# L-D5019-08-01.net
KiCad netlist of a schematic drawn in Altium Designer
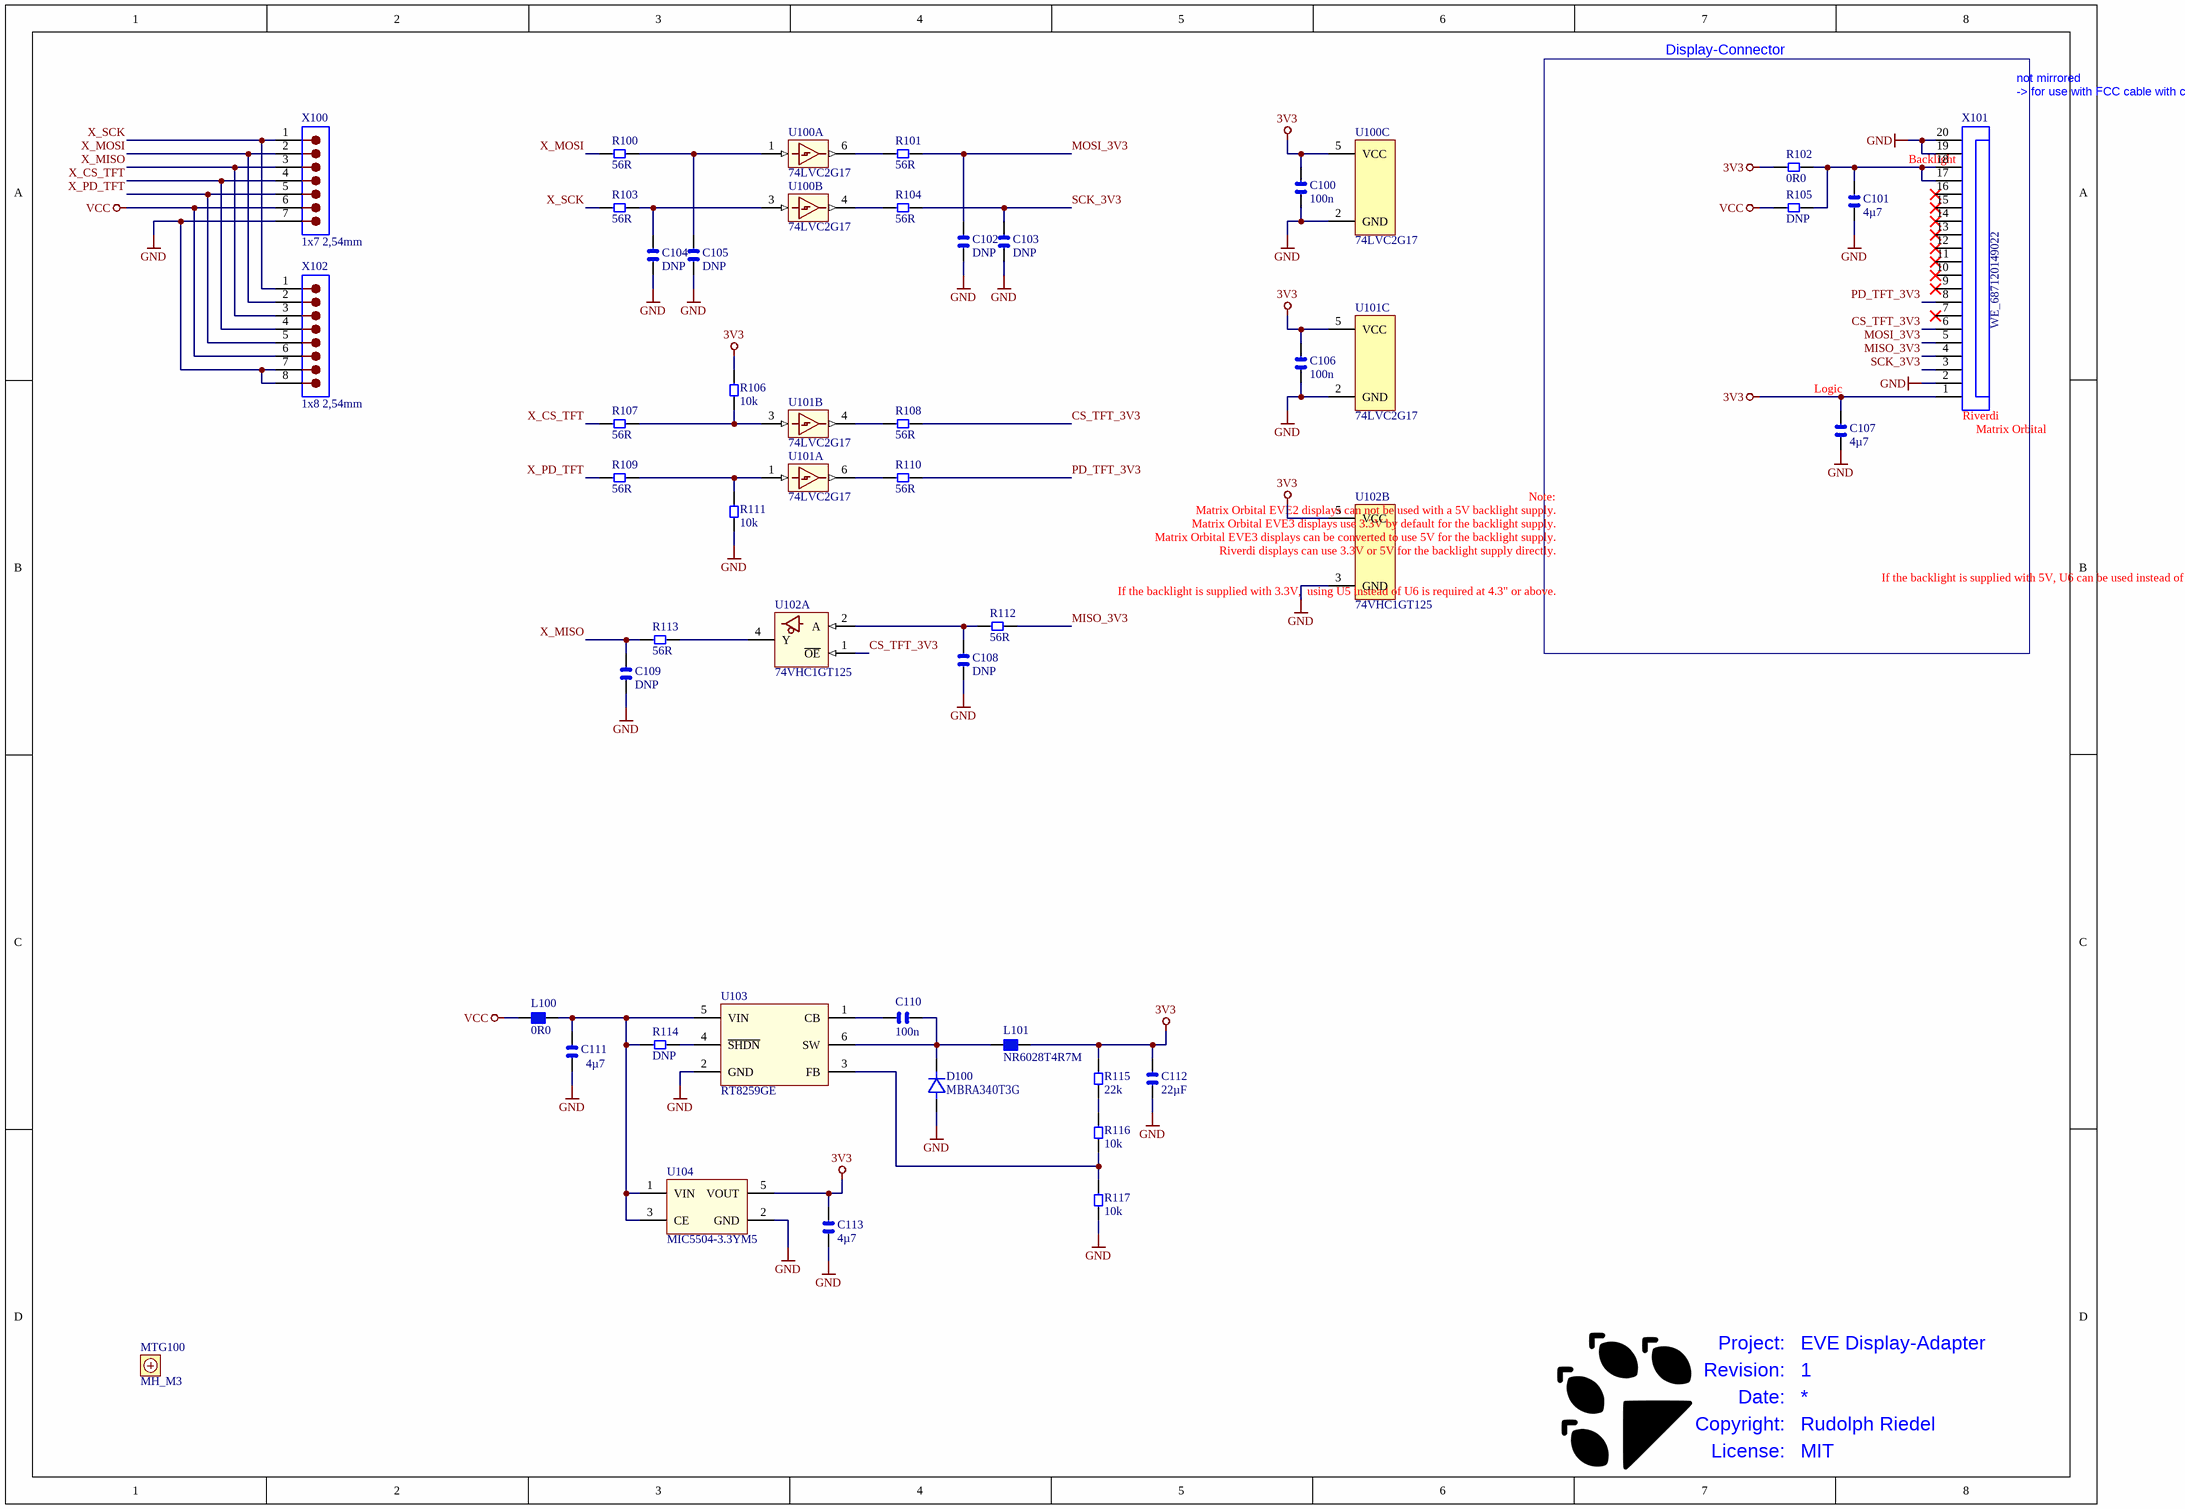
[diagram p0: L-D5019-08-01.SchDoc]

(export (version "E")
  (design (tool "Eeschema 10.0.6"))
  (components
    (comp (ref "C100")
      (value "100n")
      (footprint "CAPC2012X14L")
      (description "0805 Chip Capacitor")
      (fields (field (name "PART NUMBER") "CAPC_0805") (field (name "EDITOR") "rriedel"))
      (libsource (lib "HW-Labor_GF") (part "CAP_2_V2"))
    )
    (comp (ref "C101")
      (value "4µ7")
      (footprint "CAPC2012X14L")
      (description "0805 Chip Capacitor")
      (fields (field (name "PART NUMBER") "CAPC_0805") (field (name "ERSTELLER") "rriedel"))
      (libsource (lib "HW-Labor_GF") (part "CAP_2_V2"))
    )
    (comp (ref "C102")
      (value "DNP")
      (footprint "CAPC2012X14L")
      (description "0805 Chip Capacitor")
      (fields (field (name "PART NUMBER") "CAPC_0805") (field (name "EDITOR") "rriedel"))
      (libsource (lib "HW-Labor_GF") (part "CAP_2_V2"))
    )
    (comp (ref "C103")
      (value "DNP")
      (footprint "CAPC2012X14L")
      (description "0805 Chip Capacitor")
      (fields (field (name "PART NUMBER") "CAPC_0805") (field (name "EDITOR") "rriedel"))
      (libsource (lib "HW-Labor_GF") (part "CAP_2_V2"))
    )
    (comp (ref "C104")
      (value "DNP")
      (footprint "CAPC2012X14L")
      (description "0805 Chip Capacitor")
      (fields (field (name "PART NUMBER") "CAPC_0805") (field (name "EDITOR") "rriedel"))
      (libsource (lib "HW-Labor_GF") (part "CAP_2_V2"))
    )
    (comp (ref "C105")
      (value "DNP")
      (footprint "CAPC2012X14L")
      (description "0805 Chip Capacitor")
      (fields (field (name "PART NUMBER") "CAPC_0805") (field (name "EDITOR") "rriedel"))
      (libsource (lib "HW-Labor_GF") (part "CAP_2_V2"))
    )
    (comp (ref "C106")
      (value "100n")
      (footprint "CAPC2012X14L")
      (description "0805 Chip Capacitor")
      (fields (field (name "PART NUMBER") "CAPC_0805") (field (name "EDITOR") "rriedel"))
      (libsource (lib "HW-Labor_GF") (part "CAP_2_V2"))
    )
    (comp (ref "C107")
      (value "4µ7")
      (footprint "CAPC2012X14L")
      (description "0805 Chip Capacitor")
      (fields (field (name "PART NUMBER") "CAPC_0805") (field (name "ERSTELLER") "rriedel"))
      (libsource (lib "HW-Labor_GF") (part "CAP_2_V2"))
    )
    (comp (ref "C108")
      (value "DNP")
      (footprint "CAPC2012X14L")
      (description "0805 Chip Capacitor")
      (fields (field (name "PART NUMBER") "CAPC_0805") (field (name "EDITOR") "rriedel"))
      (libsource (lib "HW-Labor_GF") (part "CAP_2_V2"))
    )
    (comp (ref "C109")
      (value "DNP")
      (footprint "CAPC2012X14L")
      (description "0805 Chip Capacitor")
      (fields (field (name "PART NUMBER") "CAPC_0805") (field (name "EDITOR") "rriedel"))
      (libsource (lib "HW-Labor_GF") (part "CAP_2_V2"))
    )
    (comp (ref "C110")
      (value "100n")
      (footprint "CAPC2012X14L")
      (description "0805 Chip Capacitor")
      (fields (field (name "PART NUMBER") "CAPC_0805") (field (name "EDITOR") "rriedel"))
      (libsource (lib "HW-Labor_GF") (part "CAP_2_V2"))
    )
    (comp (ref "C111")
      (value "4µ7")
      (footprint "CAPC3216X19N")
      (description "1206 Chip Capacitor")
      (fields (field (name "PART NUMBER") "CAPC_1206") (field (name "EDITOR") "rriedel"))
      (libsource (lib "HW-Labor_GF") (part "CAP_2_V2"))
    )
    (comp (ref "C112")
      (value "22µF")
      (footprint "CAPC3216X19N")
      (description "1206 Chip Capacitor")
      (fields (field (name "PART NUMBER") "CAPC_1206") (field (name "EDITOR") "rriedel"))
      (libsource (lib "HW-Labor_GF") (part "CAP_2_V2"))
    )
    (comp (ref "C113")
      (value "4µ7")
      (footprint "CAPC2012X14L")
      (description "0805 Chip Capacitor")
      (fields (field (name "PART NUMBER") "CAPC_0805") (field (name "ERSTELLER") "rriedel"))
      (libsource (lib "HW-Labor_GF") (part "CAP_2_V2"))
    )
    (comp (ref "D100")
      (value "MBRA340T3G‎")
      (footprint "DIOM5226X23N")
      (description "Schottky Gleichrichterdiode, 40V / 3A / 450mV")
      (fields
        (field (name "MANUFACTURER") "ON Semiconductor")
        (field (name "DISTRIBUTOR_1_PART_NUMBER") "MBRA340T3GOSCT-ND")
        (field (name "EDITOR") "rriedel")
      )
      (libsource (lib "HW-Labor_GF") (part "Diode_A2_K1"))
    )
    (comp (ref "L100")
      (value "0R0")
      (footprint "INDC2012X10L")
      (description "0805 Chip Inductor")
      (fields (field (name "PART NUMBER") "INDC_0805") (field (name "EDITOR") "rriedel"))
      (libsource (lib "HW-Labor_GF") (part "IND_2_V1"))
    )
    (comp (ref "L101")
      (value "NR6028T4R7M")
      (footprint "TaiyoYuden_NR6028")
      (description "4,7µH, shielded, 2,7A, 40mR")
      (fields
        (field (name "MANUFACTURER") "Taiyo Yuden")
        (field (name "DISTRIBUTOR_1_PART_NUMBER") "587-2100-1-ND")
        (field (name "EDITOR") "rriedel")
      )
      (libsource (lib "HW-Labor_GF") (part "IND_2_V1"))
    )
    (comp (ref "MTG100")
      (value "MH_M3")
      (footprint "HOLE_3_2MM")
      (description "Mounting-Hole for M3 screws")
      (fields (field (name "EDITOR") "rriedel"))
      (libsource (lib "HW-Labor_GF") (part "MTG_V1"))
    )
    (comp (ref "R100")
      (value "56R")
      (footprint "RESC2012X06L")
      (description "0805 Chip Resistor")
      (fields (field (name "PART NUMBER") "RESC_0805") (field (name "EDITOR") "rriedel"))
      (libsource (lib "HW-Labor_GF") (part "RES_2_V2"))
    )
    (comp (ref "R101")
      (value "56R")
      (footprint "RESC2012X06L")
      (description "0805 Chip Resistor")
      (fields (field (name "PART NUMBER") "RESC_0805") (field (name "EDITOR") "rriedel"))
      (libsource (lib "HW-Labor_GF") (part "RES_2_V2"))
    )
    (comp (ref "R102")
      (value "0R0")
      (footprint "RESC2012X06L")
      (description "0805 Chip Resistor")
      (fields (field (name "PART NUMBER") "RESC_0805") (field (name "EDITOR") "rriedel"))
      (libsource (lib "HW-Labor_GF") (part "RES_2_V2"))
    )
    (comp (ref "R103")
      (value "56R")
      (footprint "RESC2012X06L")
      (description "0805 Chip Resistor")
      (fields (field (name "PART NUMBER") "RESC_0805") (field (name "EDITOR") "rriedel"))
      (libsource (lib "HW-Labor_GF") (part "RES_2_V2"))
    )
    (comp (ref "R104")
      (value "56R")
      (footprint "RESC2012X06L")
      (description "0805 Chip Resistor")
      (fields (field (name "PART NUMBER") "RESC_0805") (field (name "EDITOR") "rriedel"))
      (libsource (lib "HW-Labor_GF") (part "RES_2_V2"))
    )
    (comp (ref "R105")
      (value "DNP")
      (footprint "RESC2012X06L")
      (description "0805 Chip Resistor")
      (fields (field (name "PART NUMBER") "RESC_0805") (field (name "EDITOR") "rriedel"))
      (libsource (lib "HW-Labor_GF") (part "RES_2_V2"))
    )
    (comp (ref "R106")
      (value "10k")
      (footprint "RESC2012X06L")
      (description "0805 Chip Resistor")
      (fields (field (name "PART NUMBER") "RESC_0805") (field (name "EDITOR") "rriedel"))
      (libsource (lib "HW-Labor_GF") (part "RES_2_V2"))
    )
    (comp (ref "R107")
      (value "56R")
      (footprint "RESC2012X06L")
      (description "0805 Chip Resistor")
      (fields (field (name "PART NUMBER") "RESC_0805") (field (name "EDITOR") "rriedel"))
      (libsource (lib "HW-Labor_GF") (part "RES_2_V2"))
    )
    (comp (ref "R108")
      (value "56R")
      (footprint "RESC2012X06L")
      (description "0805 Chip Resistor")
      (fields (field (name "PART NUMBER") "RESC_0805") (field (name "EDITOR") "rriedel"))
      (libsource (lib "HW-Labor_GF") (part "RES_2_V2"))
    )
    (comp (ref "R109")
      (value "56R")
      (footprint "RESC2012X06L")
      (description "0805 Chip Resistor")
      (fields (field (name "PART NUMBER") "RESC_0805") (field (name "EDITOR") "rriedel"))
      (libsource (lib "HW-Labor_GF") (part "RES_2_V2"))
    )
    (comp (ref "R110")
      (value "56R")
      (footprint "RESC2012X06L")
      (description "0805 Chip Resistor")
      (fields (field (name "PART NUMBER") "RESC_0805") (field (name "EDITOR") "rriedel"))
      (libsource (lib "HW-Labor_GF") (part "RES_2_V2"))
    )
    (comp (ref "R111")
      (value "10k")
      (footprint "RESC2012X06L")
      (description "0805 Chip Resistor")
      (fields (field (name "PART NUMBER") "RESC_0805") (field (name "EDITOR") "rriedel"))
      (libsource (lib "HW-Labor_GF") (part "RES_2_V2"))
    )
    (comp (ref "R112")
      (value "56R")
      (footprint "RESC2012X06L")
      (description "0805 Chip Resistor")
      (fields (field (name "PART NUMBER") "RESC_0805") (field (name "EDITOR") "rriedel"))
      (libsource (lib "HW-Labor_GF") (part "RES_2_V2"))
    )
    (comp (ref "R113")
      (value "56R")
      (footprint "RESC2012X06L")
      (description "0805 Chip Resistor")
      (fields (field (name "PART NUMBER") "RESC_0805") (field (name "EDITOR") "rriedel"))
      (libsource (lib "HW-Labor_GF") (part "RES_2_V2"))
    )
    (comp (ref "R114")
      (value "DNP")
      (footprint "RESC2012X06L")
      (description "0805 Chip Resistor")
      (fields (field (name "PART NUMBER") "RESC_0805") (field (name "EDITOR") "rriedel"))
      (libsource (lib "HW-Labor_GF") (part "RES_2_V2"))
    )
    (comp (ref "R115")
      (value "22k")
      (footprint "RESC2012X06L")
      (description "0805 Chip Resistor")
      (fields (field (name "PART NUMBER") "RESC_0805") (field (name "EDITOR") "rriedel"))
      (libsource (lib "HW-Labor_GF") (part "RES_2_V2"))
    )
    (comp (ref "R116")
      (value "10k")
      (footprint "RESC2012X06L")
      (description "0805 Chip Resistor")
      (fields (field (name "PART NUMBER") "RESC_0805") (field (name "EDITOR") "rriedel"))
      (libsource (lib "HW-Labor_GF") (part "RES_2_V2"))
    )
    (comp (ref "R117")
      (value "10k")
      (footprint "RESC2012X06L")
      (description "0805 Chip Resistor")
      (fields (field (name "PART NUMBER") "RESC_0805") (field (name "EDITOR") "rriedel"))
      (libsource (lib "HW-Labor_GF") (part "RES_2_V2"))
    )
    (comp (ref "U100")
      (value "74LVC2G17")
      (footprint "SOT95P280X110-6N")
      (description "Dual Schmitt-Trigger Buffer with 5.5V tolerant inputs")
      (fields
        (field (name "MANUFACTURER") "TI")
        (field (name "DISTRIBUTOR_1_PART_NUMBER") "296-SN74LVC2G17DBVRCT-ND‎")
        (field (name "EDITOR") "rriedel")
      )
      (libsource (lib "HW-Labor_GF") (part "74LVC2G17"))
    )
    (comp (ref "U101")
      (value "74LVC2G17")
      (footprint "SOT95P280X110-6N")
      (description "Dual Schmitt-Trigger Buffer with 5.5V tolerant inputs")
      (fields
        (field (name "MANUFACTURER") "TI")
        (field (name "DISTRIBUTOR_1_PART_NUMBER") "296-SN74LVC2G17DBVRCT-ND‎")
        (field (name "EDITOR") "rriedel")
      )
      (libsource (lib "HW-Labor_GF") (part "74LVC2G17"))
    )
    (comp (ref "U102")
      (value "74VHC1GT125")
      (footprint "SOT95P280X110-5N")
      (description "1x Buffer with OE; 3-state,Level Shifter 3,3V to 5V and 5V to 3.3V")
      (fields
        (field (name "MANUFACTURER") "ON Semiconductor")
        (field (name "DISTRIBUTOR_1_PART_NUMBER") "1703291")
        (field (name "EDITOR") "rriedel")
      )
      (libsource (lib "") (part "74LVC1G125G_1"))
    )
    (comp (ref "U103")
      (value "RT8259GE")
      (footprint "SOT95P280X110-6N")
      (description "Step-Down DC/DC Regulator, 24V, 1.2A, 1,4MHz")
      (fields
        (field (name "MANUFACTURER") "Richtek")
        (field (name "DISTRIBUTOR_1_PART_NUMBER") "1028-1497-1-ND")
        (field (name "EDITOR") "rriedel")
      )
      (libsource (lib "HW-Labor_GF") (part "StepDown_SOT23-6"))
    )
    (comp (ref "U104")
      (value "MIC5504-3.3YM5")
      (footprint "SOT95P280X110-5N")
      (description "300 mA LDO,  Vin=2,5V…5,5V, Vout= 3,3V, -40°C..125°C")
      (fields
        (field (name "MANUFACTURER") "Microchip")
        (field (name "DISTRIBUTOR_1_PART_NUMBER") "2510377")
        (field (name "EDITOR") "rriedel")
      )
      (libsource (lib "HW-Labor_GF") (part "LDO_SOT23-5"))
    )
    (comp (ref "X100")
      (value "1x7 2,54mm")
      (footprint "PINH_1x07_2_54mm")
      (description "Pin-Header 2,54 mm 7pins")
      (fields (field (name "PART NUMBER") "PINH_1x7_2_54") (field (name "EDITOR") "rriedel"))
      (libsource (lib "HW-Labor_GF") (part "CONM_1x7_V2"))
    )
    (comp (ref "X101")
      (value "WE_687120149022")
      (footprint "WE_687120149022")
      (description "20pin WR-FPC 0.50 mm SMT ZIF Horizontal - Bottom Contact")
      (fields
        (field (name "MANUFACTURER") "Wuerth")
        (field (name "DISTRIBUTOR_1_PART_NUMBER") "732-6002-1-ND")
        (field (name "EDITOR") "rriedel")
      )
      (libsource (lib "HW-Labor_GF") (part "FPC_20"))
    )
    (comp (ref "X102")
      (value "1x8 2,54mm")
      (footprint "PINH_1x08_2_54mm")
      (description "Pin-Header 2,54 mm 8pins")
      (fields (field (name "PART NUMBER") "PINH_1x8_2_54") (field (name "EDITOR") "rriedel"))
      (libsource (lib "HW-Labor_GF") (part "CONM_1x8_V2"))
    )
  )
  (nets
    (net (code "1") (name "/CS_TFT_3V3") (class "Default")
      (node (ref "R108") (pin "2") (pinfunction "2_2") (pintype "passive"))
      (node (ref "U102") (pin "1") (pinfunction "~{OE}_1") (pintype "input"))
      (node (ref "X101") (pin "6") (pinfunction "6_6") (pintype "passive"))
    )
    (net (code "2") (name "/MISO_3V3") (class "Default")
      (node (ref "R112") (pin "2") (pinfunction "2_2") (pintype "passive"))
      (node (ref "X101") (pin "4") (pinfunction "4_4") (pintype "passive"))
    )
    (net (code "3") (name "/MOSI_3V3") (class "Default")
      (node (ref "C102") (pin "2") (pinfunction "2_2") (pintype "passive"))
      (node (ref "R101") (pin "2") (pinfunction "2_2") (pintype "passive"))
      (node (ref "X101") (pin "5") (pinfunction "5_5") (pintype "passive"))
    )
    (net (code "4") (name "/PD_TFT_3V3") (class "Default")
      (node (ref "R110") (pin "2") (pinfunction "2_2") (pintype "passive"))
      (node (ref "X101") (pin "8") (pinfunction "8_8") (pintype "passive"))
    )
    (net (code "5") (name "/SCK_3V3") (class "Default")
      (node (ref "C103") (pin "2") (pinfunction "2_2") (pintype "passive"))
      (node (ref "R104") (pin "2") (pinfunction "2_2") (pintype "passive"))
      (node (ref "X101") (pin "3") (pinfunction "3_3") (pintype "passive"))
    )
    (net (code "6") (name "/X_CS_TFT") (class "Default")
      (node (ref "R107") (pin "1") (pinfunction "1_1") (pintype "passive"))
      (node (ref "X100") (pin "4") (pinfunction "4_4") (pintype "passive"))
      (node (ref "X102") (pin "4") (pinfunction "4_4") (pintype "passive"))
    )
    (net (code "7") (name "/X_MISO") (class "Default")
      (node (ref "C109") (pin "2") (pinfunction "2_2") (pintype "passive"))
      (node (ref "R113") (pin "1") (pinfunction "1_1") (pintype "passive"))
      (node (ref "X100") (pin "3") (pinfunction "3_3") (pintype "passive"))
      (node (ref "X102") (pin "3") (pinfunction "3_3") (pintype "passive"))
    )
    (net (code "8") (name "/X_MOSI") (class "Default")
      (node (ref "R100") (pin "1") (pinfunction "1_1") (pintype "passive"))
      (node (ref "X100") (pin "2") (pinfunction "2_2") (pintype "passive"))
      (node (ref "X102") (pin "2") (pinfunction "2_2") (pintype "passive"))
    )
    (net (code "9") (name "/X_PD_TFT") (class "Default")
      (node (ref "R109") (pin "1") (pinfunction "1_1") (pintype "passive"))
      (node (ref "X100") (pin "5") (pinfunction "5_5") (pintype "passive"))
      (node (ref "X102") (pin "5") (pinfunction "5_5") (pintype "passive"))
    )
    (net (code "10") (name "/X_SCK") (class "Default")
      (node (ref "R103") (pin "1") (pinfunction "1_1") (pintype "passive"))
      (node (ref "X100") (pin "1") (pinfunction "1_1") (pintype "passive"))
      (node (ref "X102") (pin "1") (pinfunction "1_1") (pintype "passive"))
    )
    (net (code "11") (name "3V3") (class "Default")
      (node (ref "C100") (pin "2") (pinfunction "2_2") (pintype "passive"))
      (node (ref "C106") (pin "2") (pinfunction "2_2") (pintype "passive"))
      (node (ref "C107") (pin "2") (pinfunction "2_2") (pintype "passive"))
      (node (ref "C112") (pin "2") (pinfunction "2_2") (pintype "passive"))
      (node (ref "C113") (pin "2") (pinfunction "2_2") (pintype "passive"))
      (node (ref "L101") (pin "2") (pinfunction "2_2") (pintype "passive"))
      (node (ref "R102") (pin "1") (pinfunction "1_1") (pintype "passive"))
      (node (ref "R106") (pin "2") (pinfunction "2_2") (pintype "passive"))
      (node (ref "R115") (pin "2") (pinfunction "2_2") (pintype "passive"))
      (node (ref "U100") (pin "5") (pinfunction "VCC_5") (pintype "power_in"))
      (node (ref "U101") (pin "5") (pinfunction "VCC_5") (pintype "power_in"))
      (node (ref "U102") (pin "5") (pinfunction "VCC_5") (pintype "passive"))
      (node (ref "U104") (pin "5") (pinfunction "VOUT_5") (pintype "passive"))
      (node (ref "X101") (pin "1") (pinfunction "1_1") (pintype "passive"))
    )
    (net (code "12") (name "GND") (class "Default")
      (node (ref "C100") (pin "1") (pinfunction "1_1") (pintype "passive"))
      (node (ref "C101") (pin "1") (pinfunction "1_1") (pintype "passive"))
      (node (ref "C102") (pin "1") (pinfunction "1_1") (pintype "passive"))
      (node (ref "C103") (pin "1") (pinfunction "1_1") (pintype "passive"))
      (node (ref "C104") (pin "1") (pinfunction "1_1") (pintype "passive"))
      (node (ref "C105") (pin "1") (pinfunction "1_1") (pintype "passive"))
      (node (ref "C106") (pin "1") (pinfunction "1_1") (pintype "passive"))
      (node (ref "C107") (pin "1") (pinfunction "1_1") (pintype "passive"))
      (node (ref "C108") (pin "1") (pinfunction "1_1") (pintype "passive"))
      (node (ref "C109") (pin "1") (pinfunction "1_1") (pintype "passive"))
      (node (ref "C111") (pin "1") (pinfunction "1_1") (pintype "passive"))
      (node (ref "C112") (pin "1") (pinfunction "1_1") (pintype "passive"))
      (node (ref "C113") (pin "1") (pinfunction "1_1") (pintype "passive"))
      (node (ref "D100") (pin "2") (pinfunction "2_2") (pintype "passive"))
      (node (ref "R111") (pin "1") (pinfunction "1_1") (pintype "passive"))
      (node (ref "R117") (pin "1") (pinfunction "1_1") (pintype "passive"))
      (node (ref "U100") (pin "2") (pinfunction "GND_2") (pintype "power_in"))
      (node (ref "U101") (pin "2") (pinfunction "GND_2") (pintype "power_in"))
      (node (ref "U102") (pin "3") (pinfunction "GND_3") (pintype "passive"))
      (node (ref "U103") (pin "2") (pinfunction "GND_2") (pintype "power_in"))
      (node (ref "U104") (pin "2") (pinfunction "GND_2") (pintype "passive"))
      (node (ref "X100") (pin "7") (pinfunction "7_7") (pintype "passive"))
      (node (ref "X101") (pin "19") (pinfunction "19_19") (pintype "passive"))
      (node (ref "X101") (pin "2") (pinfunction "2_2") (pintype "passive"))
      (node (ref "X101") (pin "20") (pinfunction "20_20") (pintype "passive"))
      (node (ref "X102") (pin "7") (pinfunction "7_7") (pintype "passive"))
      (node (ref "X102") (pin "8") (pinfunction "8_8") (pintype "passive"))
    )
    (net (code "13") (name "Net-(C101-Pad2)") (class "Default")
      (node (ref "C101") (pin "2") (pinfunction "2_2") (pintype "passive"))
      (node (ref "R102") (pin "2") (pinfunction "2_2") (pintype "passive"))
      (node (ref "R105") (pin "2") (pinfunction "2_2") (pintype "passive"))
      (node (ref "X101") (pin "17") (pinfunction "17_17") (pintype "passive"))
      (node (ref "X101") (pin "18") (pinfunction "18_18") (pintype "passive"))
    )
    (net (code "14") (name "Net-(R115-Pad1)") (class "Default")
      (node (ref "R115") (pin "1") (pinfunction "1_1") (pintype "passive"))
      (node (ref "R116") (pin "2") (pinfunction "2_2") (pintype "passive"))
    )
    (net (code "15") (name "Net-(U100A-1A)") (class "Default")
      (node (ref "C105") (pin "2") (pinfunction "2_2") (pintype "passive"))
      (node (ref "R100") (pin "2") (pinfunction "2_2") (pintype "passive"))
      (node (ref "U100") (pin "1") (pinfunction "1A_1") (pintype "input"))
    )
    (net (code "16") (name "Net-(U100A-1Y)") (class "Default")
      (node (ref "R101") (pin "1") (pinfunction "1_1") (pintype "passive"))
      (node (ref "U100") (pin "6") (pinfunction "1Y_6") (pintype "output"))
    )
    (net (code "17") (name "Net-(U100B-2A)") (class "Default")
      (node (ref "C104") (pin "2") (pinfunction "2_2") (pintype "passive"))
      (node (ref "R103") (pin "2") (pinfunction "2_2") (pintype "passive"))
      (node (ref "U100") (pin "3") (pinfunction "2A_3") (pintype "input"))
    )
    (net (code "18") (name "Net-(U100B-2Y)") (class "Default")
      (node (ref "R104") (pin "1") (pinfunction "1_1") (pintype "passive"))
      (node (ref "U100") (pin "4") (pinfunction "2Y_4") (pintype "output"))
    )
    (net (code "19") (name "Net-(U101A-1A)") (class "Default")
      (node (ref "R109") (pin "2") (pinfunction "2_2") (pintype "passive"))
      (node (ref "R111") (pin "2") (pinfunction "2_2") (pintype "passive"))
      (node (ref "U101") (pin "1") (pinfunction "1A_1") (pintype "input"))
    )
    (net (code "20") (name "Net-(U101A-1Y)") (class "Default")
      (node (ref "R110") (pin "1") (pinfunction "1_1") (pintype "passive"))
      (node (ref "U101") (pin "6") (pinfunction "1Y_6") (pintype "output"))
    )
    (net (code "21") (name "Net-(U101B-2A)") (class "Default")
      (node (ref "R106") (pin "1") (pinfunction "1_1") (pintype "passive"))
      (node (ref "R107") (pin "2") (pinfunction "2_2") (pintype "passive"))
      (node (ref "U101") (pin "3") (pinfunction "2A_3") (pintype "input"))
    )
    (net (code "22") (name "Net-(U101B-2Y)") (class "Default")
      (node (ref "R108") (pin "1") (pinfunction "1_1") (pintype "passive"))
      (node (ref "U101") (pin "4") (pinfunction "2Y_4") (pintype "output"))
    )
    (net (code "23") (name "Net-(U102A-A)") (class "Default")
      (node (ref "C108") (pin "2") (pinfunction "2_2") (pintype "passive"))
      (node (ref "R112") (pin "1") (pinfunction "1_1") (pintype "passive"))
      (node (ref "U102") (pin "2") (pinfunction "A_2") (pintype "input"))
    )
    (net (code "24") (name "Net-(U102A-Y)") (class "Default")
      (node (ref "R113") (pin "2") (pinfunction "2_2") (pintype "passive"))
      (node (ref "U102") (pin "4") (pinfunction "Y_4") (pintype "tri_state"))
    )
    (net (code "25") (name "Net-(U103-CB)") (class "Default")
      (node (ref "C110") (pin "1") (pinfunction "1_1") (pintype "passive"))
      (node (ref "U103") (pin "1") (pinfunction "CB_1") (pintype "passive"))
    )
    (net (code "26") (name "Net-(U103-FB)") (class "Default")
      (node (ref "R116") (pin "1") (pinfunction "1_1") (pintype "passive"))
      (node (ref "R117") (pin "2") (pinfunction "2_2") (pintype "passive"))
      (node (ref "U103") (pin "3") (pinfunction "FB_3") (pintype "passive"))
    )
    (net (code "27") (name "Net-(U103-SW)") (class "Default")
      (node (ref "C110") (pin "2") (pinfunction "2_2") (pintype "passive"))
      (node (ref "D100") (pin "1") (pinfunction "1_1") (pintype "passive"))
      (node (ref "L101") (pin "1") (pinfunction "1_1") (pintype "passive"))
      (node (ref "U103") (pin "6") (pinfunction "SW_6") (pintype "passive"))
    )
    (net (code "28") (name "Net-(U103-VIN)") (class "Default")
      (node (ref "C111") (pin "2") (pinfunction "2_2") (pintype "passive"))
      (node (ref "L100") (pin "2") (pinfunction "2_2") (pintype "passive"))
      (node (ref "R114") (pin "1") (pinfunction "1_1") (pintype "passive"))
      (node (ref "U103") (pin "5") (pinfunction "VIN_5") (pintype "power_in"))
      (node (ref "U104") (pin "1") (pinfunction "VIN_1") (pintype "passive"))
      (node (ref "U104") (pin "3") (pinfunction "CE_3") (pintype "passive"))
    )
    (net (code "29") (name "Net-(U103-~{SHDN})") (class "Default")
      (node (ref "R114") (pin "2") (pinfunction "2_2") (pintype "passive"))
      (node (ref "U103") (pin "4") (pinfunction "~{SHDN}_4") (pintype "passive"))
    )
    (net (code "30") (name "VCC") (class "Default")
      (node (ref "L100") (pin "1") (pinfunction "1_1") (pintype "passive"))
      (node (ref "R105") (pin "1") (pinfunction "1_1") (pintype "passive"))
      (node (ref "X100") (pin "6") (pinfunction "6_6") (pintype "passive"))
      (node (ref "X102") (pin "6") (pinfunction "6_6") (pintype "passive"))
    )
    (net (code "31") (name "unconnected-(X101-Pad7)") (class "Default")
      (node (ref "X101") (pin "7") (pinfunction "7_7") (pintype "passive+no_connect"))
    )
    (net (code "32") (name "unconnected-(X101-Pad9)") (class "Default")
      (node (ref "X101") (pin "9") (pinfunction "9_9") (pintype "passive+no_connect"))
    )
    (net (code "33") (name "unconnected-(X101-Pad10)") (class "Default")
      (node (ref "X101") (pin "10") (pinfunction "10_10") (pintype "passive+no_connect"))
    )
    (net (code "34") (name "unconnected-(X101-Pad11)") (class "Default")
      (node (ref "X101") (pin "11") (pinfunction "11_11") (pintype "passive+no_connect"))
    )
    (net (code "35") (name "unconnected-(X101-Pad12)") (class "Default")
      (node (ref "X101") (pin "12") (pinfunction "12_12") (pintype "passive+no_connect"))
    )
    (net (code "36") (name "unconnected-(X101-Pad13)") (class "Default")
      (node (ref "X101") (pin "13") (pinfunction "13_13") (pintype "passive+no_connect"))
    )
    (net (code "37") (name "unconnected-(X101-Pad14)") (class "Default")
      (node (ref "X101") (pin "14") (pinfunction "14_14") (pintype "passive+no_connect"))
    )
    (net (code "38") (name "unconnected-(X101-Pad15)") (class "Default")
      (node (ref "X101") (pin "15") (pinfunction "15_15") (pintype "passive+no_connect"))
    )
    (net (code "39") (name "unconnected-(X101-Pad16)") (class "Default")
      (node (ref "X101") (pin "16") (pinfunction "16_16") (pintype "passive+no_connect"))
    )
  )
)
